# Clock_Flash_Verified.net
KiCad netlist of a schematic drawn in Altium Designer
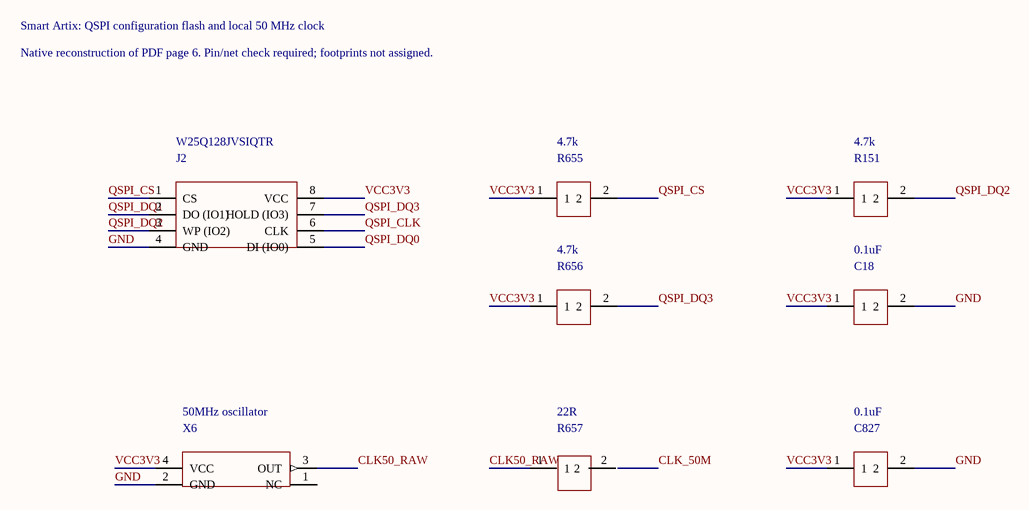
[diagram p0: Clock_Flash_Verified.SchDoc]

(export (version "E")
  (design (tool "Eeschema 10.0.6"))
  (components
    (comp (ref "C18")
      (value "0.1uF")
      (description "Reconstructed from Smart Artix reference PDF")
      (libsource (lib "*") (part "0.1uF"))
    )
    (comp (ref "C827")
      (value "0.1uF")
      (description "Reconstructed from Smart Artix reference PDF")
      (libsource (lib "*") (part "0.1uF"))
    )
    (comp (ref "J2")
      (value "W25Q128JVSIQTR")
      (description "Reconstructed from Smart Artix reference PDF")
      (libsource (lib "*") (part "W25Q128JVSIQTR"))
    )
    (comp (ref "R151")
      (value "4.7k")
      (description "Reconstructed from Smart Artix reference PDF")
      (libsource (lib "*") (part "4.7k"))
    )
    (comp (ref "R655")
      (value "4.7k")
      (description "Reconstructed from Smart Artix reference PDF")
      (libsource (lib "*") (part "4.7k"))
    )
    (comp (ref "R656")
      (value "4.7k")
      (description "Reconstructed from Smart Artix reference PDF")
      (libsource (lib "*") (part "4.7k"))
    )
    (comp (ref "R657")
      (value "22R")
      (description "Reconstructed from Smart Artix reference PDF")
      (libsource (lib "*") (part "22R"))
    )
    (comp (ref "X6")
      (value "50MHz oscillator")
      (description "Reconstructed from Smart Artix reference PDF")
      (libsource (lib "*") (part "50MHz oscillator"))
    )
  )
  (nets
    (net (code "1") (name "/CLK50_RAW") (class "Default")
      (node (ref "R657") (pin "1") (pinfunction "1_1") (pintype "passive"))
      (node (ref "X6") (pin "3") (pinfunction "OUT_3") (pintype "output"))
    )
    (net (code "3") (name "/GND") (class "Default")
      (node (ref "C18") (pin "2") (pinfunction "2_2") (pintype "passive"))
      (node (ref "C827") (pin "2") (pinfunction "2_2") (pintype "passive"))
      (node (ref "J2") (pin "4") (pinfunction "GND_4") (pintype "power_in"))
      (node (ref "X6") (pin "2") (pinfunction "GND_2") (pintype "power_in"))
    )
    (net (code "4") (name "/QSPI_CLK") (class "Default")
      (node (ref "J2") (pin "6") (pinfunction "CLK_6") (pintype "passive"))
    )
    (net (code "5") (name "/QSPI_CS") (class "Default")
      (node (ref "J2") (pin "1") (pinfunction "CS_1") (pintype "passive"))
      (node (ref "R655") (pin "2") (pinfunction "2_2") (pintype "passive"))
    )
    (net (code "6") (name "/QSPI_DQ0") (class "Default")
      (node (ref "J2") (pin "5") (pinfunction "DI_(IO0)_5") (pintype "passive"))
    )
    (net (code "7") (name "/QSPI_DQ1") (class "Default")
      (node (ref "J2") (pin "2") (pinfunction "DO_(IO1)_2") (pintype "passive"))
    )
    (net (code "8") (name "/QSPI_DQ2") (class "Default")
      (node (ref "J2") (pin "3") (pinfunction "WP_(IO2)_3") (pintype "passive"))
      (node (ref "R151") (pin "2") (pinfunction "2_2") (pintype "passive"))
    )
    (net (code "9") (name "/QSPI_DQ3") (class "Default")
      (node (ref "J2") (pin "7") (pinfunction "HOLD_(IO3)_7") (pintype "passive"))
      (node (ref "R656") (pin "2") (pinfunction "2_2") (pintype "passive"))
    )
    (net (code "10") (name "/VCC3V3") (class "Default")
      (node (ref "C18") (pin "1") (pinfunction "1_1") (pintype "passive"))
      (node (ref "C827") (pin "1") (pinfunction "1_1") (pintype "passive"))
      (node (ref "J2") (pin "8") (pinfunction "VCC_8") (pintype "power_in"))
      (node (ref "R151") (pin "1") (pinfunction "1_1") (pintype "passive"))
      (node (ref "R655") (pin "1") (pinfunction "1_1") (pintype "passive"))
      (node (ref "R656") (pin "1") (pinfunction "1_1") (pintype "passive"))
      (node (ref "X6") (pin "4") (pinfunction "VCC_4") (pintype "power_in"))
    )
    (net (code "11") (name "unconnected-(R657-Pad2)") (class "Default")
      (node (ref "R657") (pin "2") (pinfunction "2_2") (pintype "passive"))
    )
    (net (code "12") (name "unconnected-(X6-NC-Pad1)") (class "Default")
      (node (ref "X6") (pin "1") (pinfunction "NC_1") (pintype "passive"))
    )
  )
)
